# E-P-204-R3_4.net
KiCad netlist of a schematic drawn in EAGLE
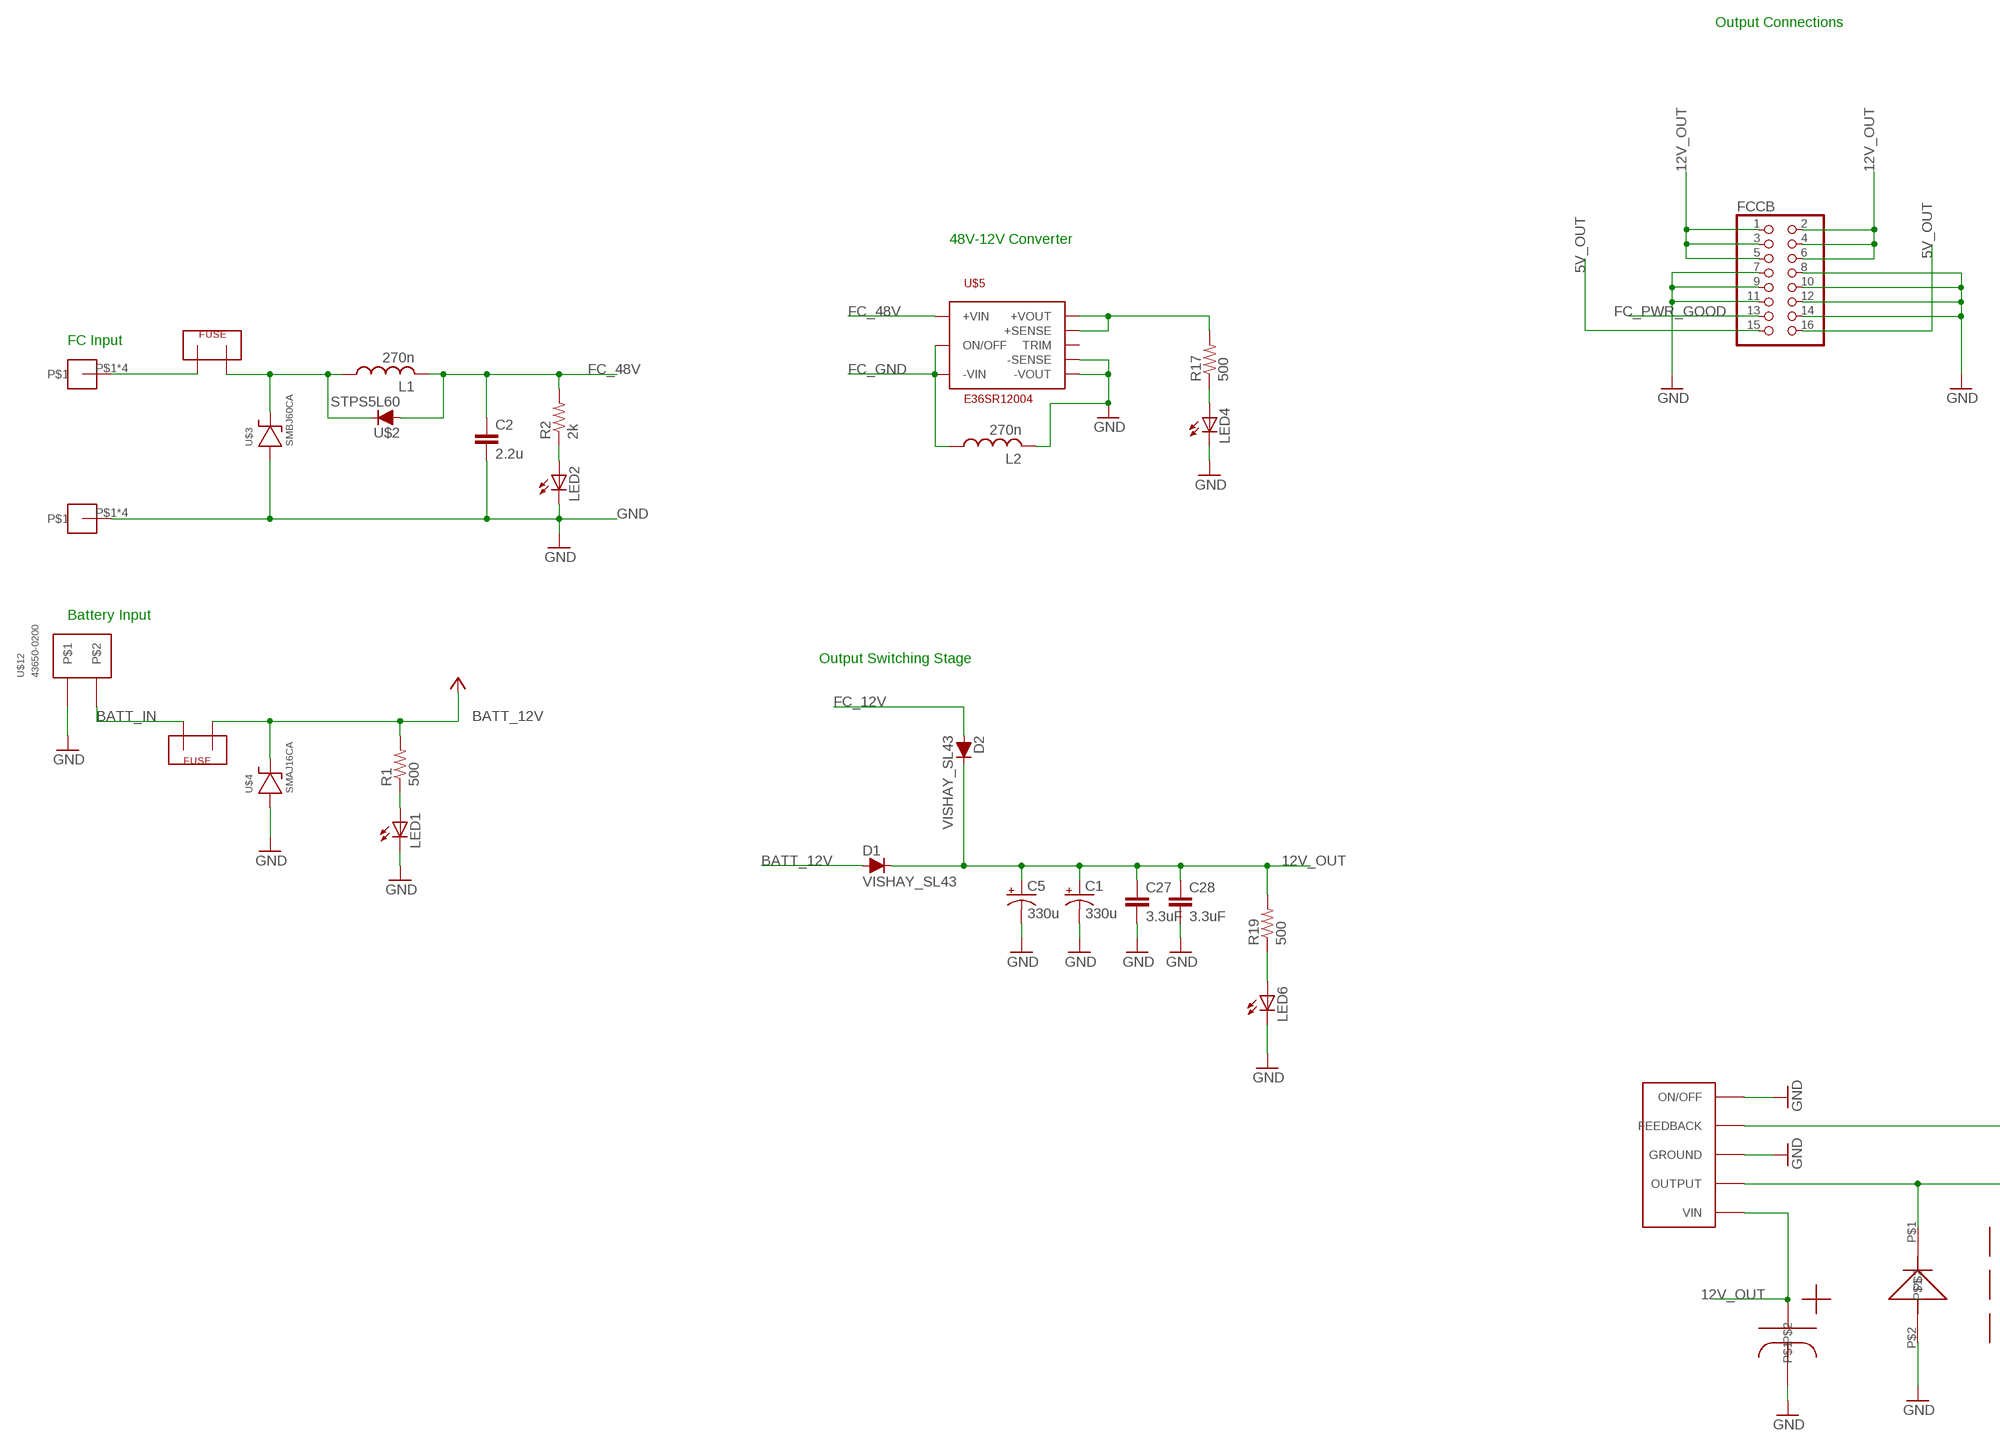
[diagram p0: schematic, sheet 1, part 1 of 2]
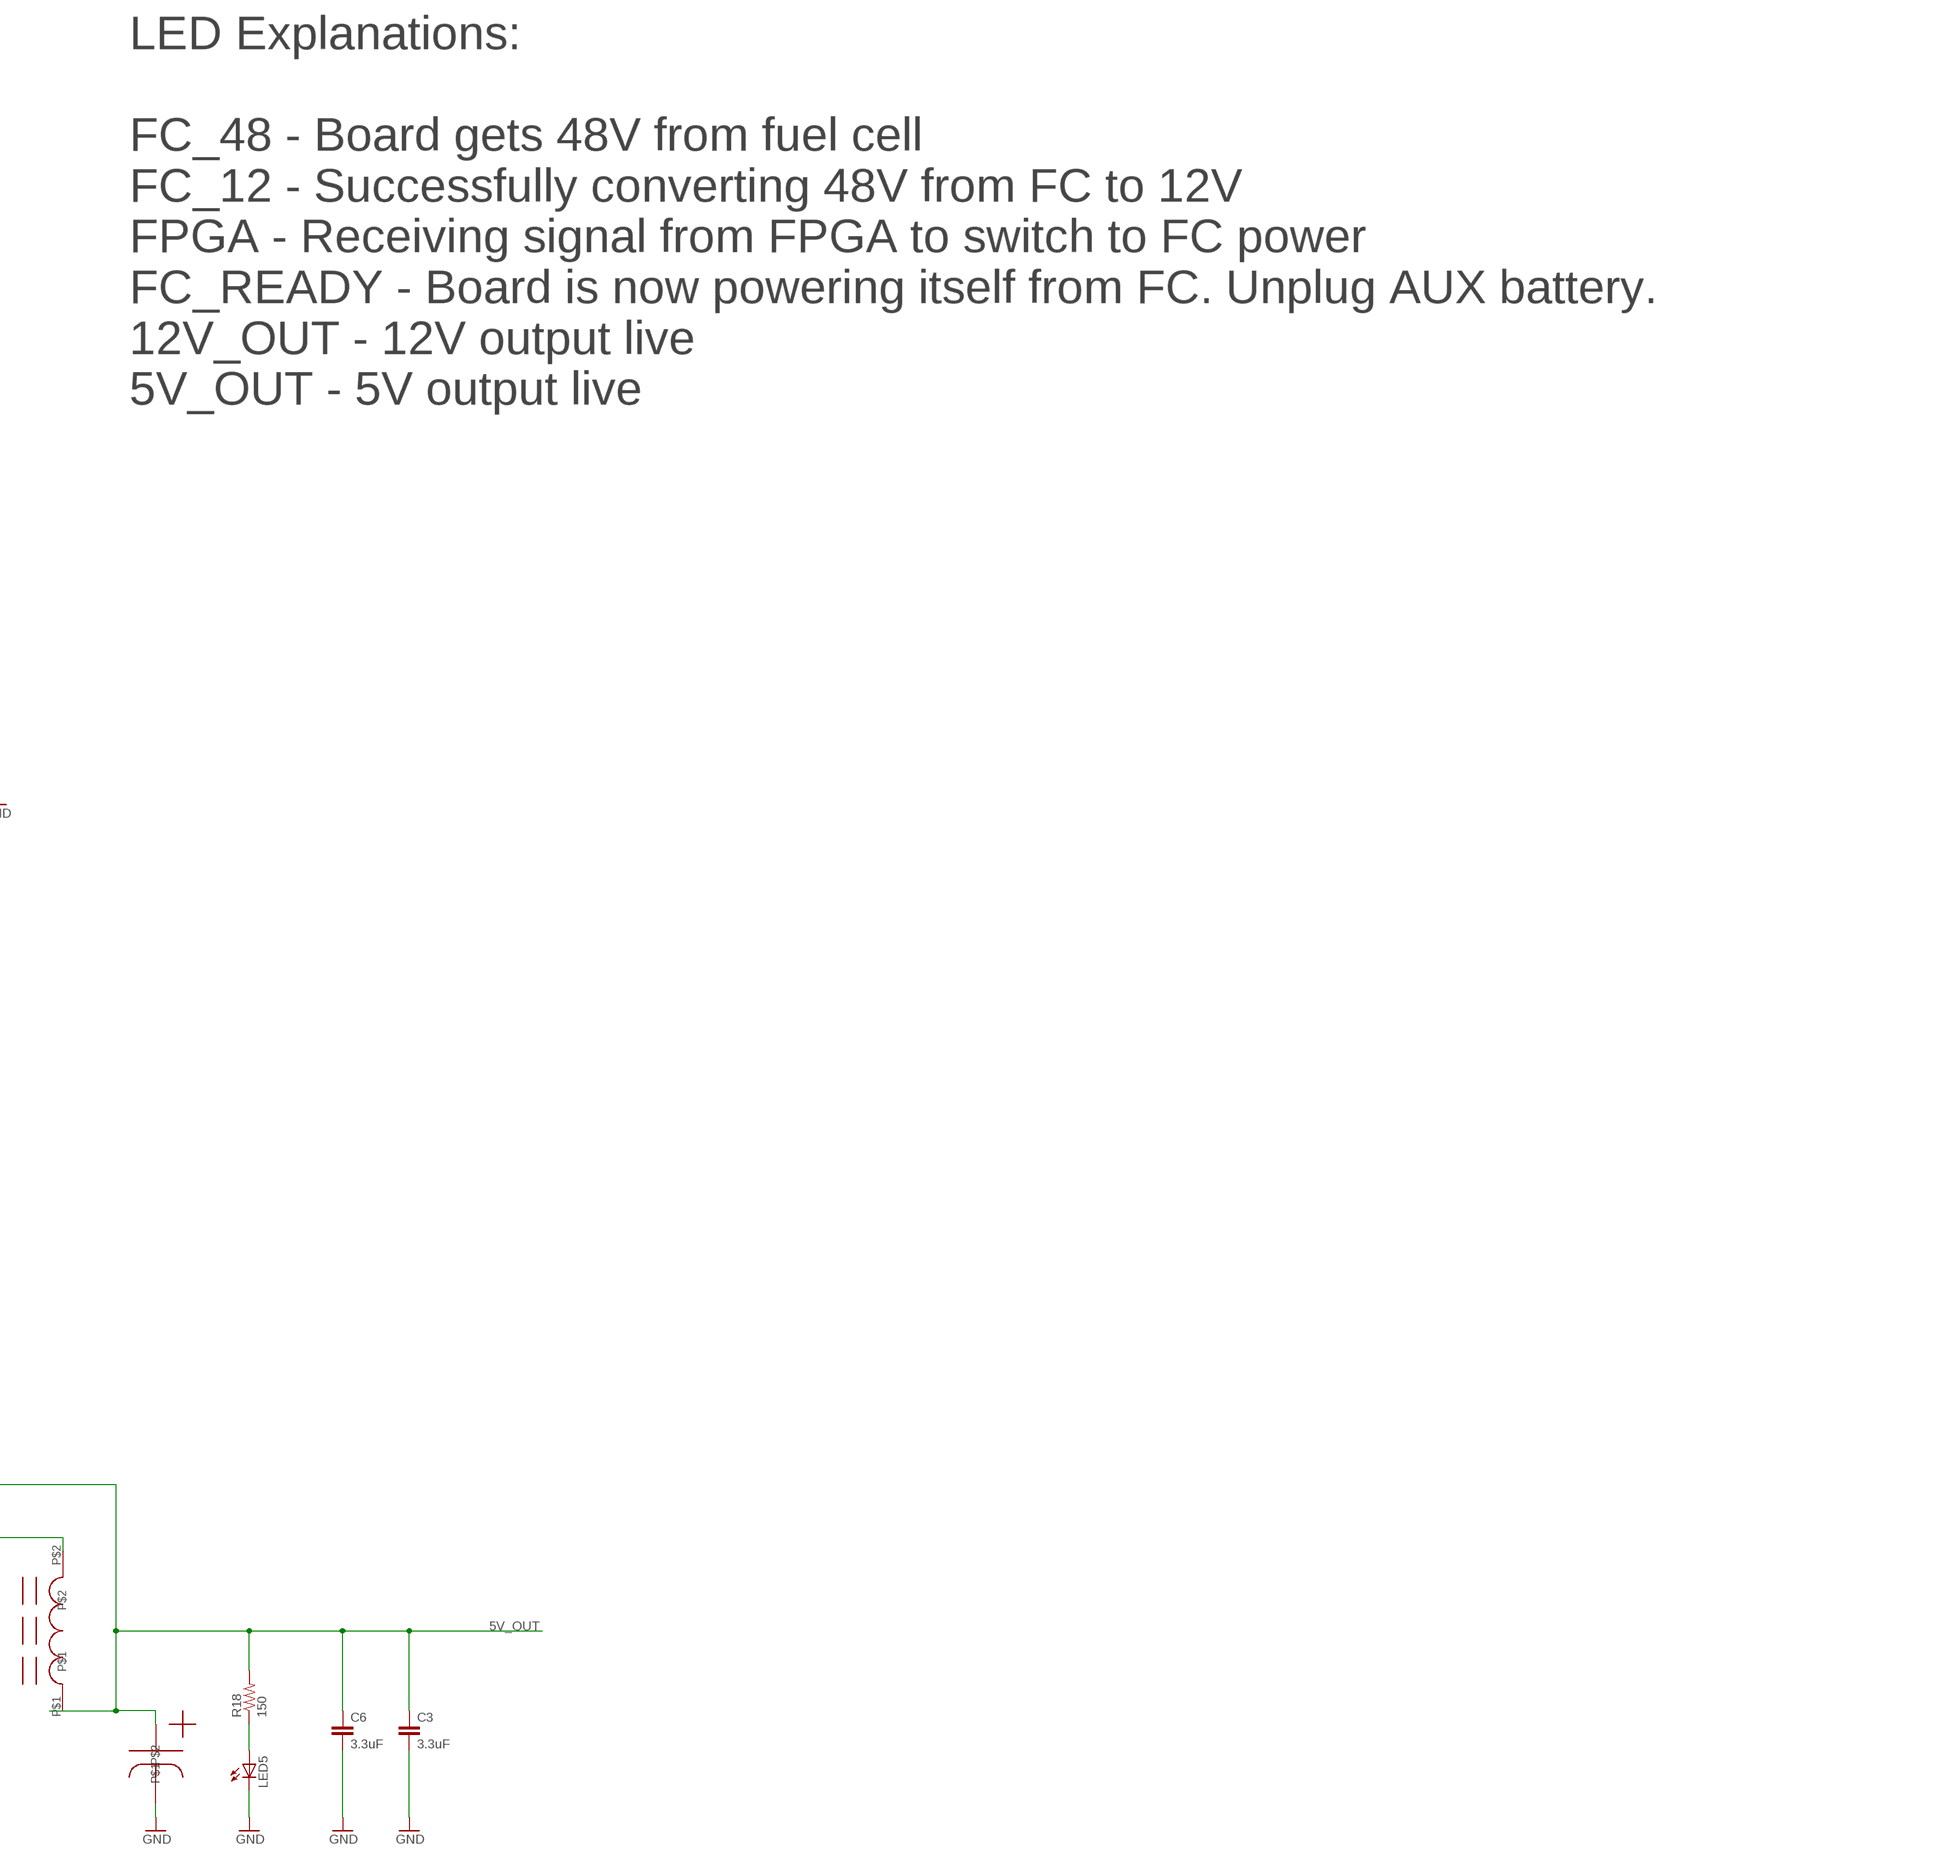
[diagram p1: schematic, sheet 1, part 2 of 2]

(export (version "E")
  (design (tool "Eeschema 10.0.6"))
  (components
    (comp (ref "C1")
      (value "330u")
      (footprint "eagle-import:PANASONIC_E")
      (libsource (lib "eagle-import") (part "CAP_POLE"))
    )
    (comp (ref "C2")
      (value "2.2u")
      (footprint "eagle-import:C1210")
      (libsource (lib "eagle-import") (part "C-EUC1210"))
    )
    (comp (ref "C3")
      (value "3.3uF")
      (footprint "eagle-import:C0805K")
      (libsource (lib "eagle-import") (part "C-EUC0805K"))
    )
    (comp (ref "C5")
      (value "330u")
      (footprint "eagle-import:PANASONIC_E")
      (libsource (lib "eagle-import") (part "CAP_POLE"))
    )
    (comp (ref "C6")
      (value "3.3uF")
      (footprint "eagle-import:C0805K")
      (libsource (lib "eagle-import") (part "C-EUC0805K"))
    )
    (comp (ref "C27")
      (value "3.3uF")
      (footprint "eagle-import:C0805K")
      (libsource (lib "eagle-import") (part "C-EUC0805K"))
    )
    (comp (ref "C28")
      (value "3.3uF")
      (footprint "eagle-import:C0805K")
      (libsource (lib "eagle-import") (part "C-EUC0805K"))
    )
    (comp (ref "D1")
      (value "VISHAY_SL43")
      (footprint "eagle-import:DO-214AB_SMC")
      (libsource (lib "eagle-import") (part "VISHAY_SL43"))
    )
    (comp (ref "D2")
      (value "VISHAY_SL43")
      (footprint "eagle-import:DO-214AB_SMC")
      (libsource (lib "eagle-import") (part "VISHAY_SL43"))
    )
    (comp (ref "FCCB")
      (value "PINHD-2X8")
      (footprint "eagle-import:2X08")
      (libsource (lib "eagle-import") (part "PINHD-2X8"))
    )
    (comp (ref "L1")
      (value "270n")
      (footprint "eagle-import:L3225P")
      (libsource (lib "eagle-import") (part "L-USL3225P"))
    )
    (comp (ref "L2")
      (value "270n")
      (footprint "eagle-import:L3225P")
      (libsource (lib "eagle-import") (part "L-USL3225P"))
    )
    (comp (ref "LED1")
      (value "LED1206")
      (footprint "eagle-import:LED-1206")
      (libsource (lib "eagle-import") (part "LED1206"))
    )
    (comp (ref "LED2")
      (value "LED1206")
      (footprint "eagle-import:LED-1206")
      (libsource (lib "eagle-import") (part "LED1206"))
    )
    (comp (ref "LED4")
      (value "LED1206")
      (footprint "eagle-import:LED-1206")
      (libsource (lib "eagle-import") (part "LED1206"))
    )
    (comp (ref "LED5")
      (value "LED1206")
      (footprint "eagle-import:LED-1206")
      (libsource (lib "eagle-import") (part "LED1206"))
    )
    (comp (ref "LED6")
      (value "LED1206")
      (footprint "eagle-import:LED-1206")
      (libsource (lib "eagle-import") (part "LED1206"))
    )
    (comp (ref "R1")
      (value "500")
      (footprint "eagle-import:M0805")
      (libsource (lib "eagle-import") (part "R-US_M0805"))
    )
    (comp (ref "R2")
      (value "2k")
      (footprint "eagle-import:M0805")
      (libsource (lib "eagle-import") (part "R-US_M0805"))
    )
    (comp (ref "R17")
      (value "500")
      (footprint "eagle-import:M0805")
      (libsource (lib "eagle-import") (part "R-US_M0805"))
    )
    (comp (ref "R18")
      (value "150")
      (footprint "eagle-import:M0805")
      (libsource (lib "eagle-import") (part "R-US_M0805"))
    )
    (comp (ref "R19")
      (value "500")
      (footprint "eagle-import:M0805")
      (libsource (lib "eagle-import") (part "R-US_M0805"))
    )
    (comp (ref "U$2")
      (value "STPS5L60")
      (footprint "eagle-import:STM_SMC")
      (libsource (lib "eagle-import") (part "STPS5L60"))
    )
    (comp (ref "U$3")
      (value "SMBJ60CA")
      (footprint "eagle-import:.277X.089")
      (libsource (lib "eagle-import") (part "SMBJ60CA"))
    )
    (comp (ref "U$4")
      (value "SMAJ16CA")
      (footprint "eagle-import:.25X.07")
      (libsource (lib "eagle-import") (part "SMAJ16CA"))
    )
    (comp (ref "U$5")
      (value "E36SR12004")
      (footprint "eagle-import:2.30X0.90X0.34")
      (libsource (lib "eagle-import") (part "E36SR12004"))
    )
    (comp (ref "U$6")
      (value "SCREW-8191")
      (footprint "eagle-import:SCREW-8191")
      (libsource (lib "eagle-import") (part "SCREW-8191"))
    )
    (comp (ref "U$7")
      (value "FUSEMINI-BLADE")
      (footprint "eagle-import:MINI-BLADE-FUSE")
      (libsource (lib "eagle-import") (part "FUSEMINI-BLADE"))
    )
    (comp (ref "U$8")
      (value "SCREW-8191")
      (footprint "eagle-import:SCREW-8191")
      (libsource (lib "eagle-import") (part "SCREW-8191"))
    )
    (comp (ref "U$9")
      (value "MBR360GOS")
      (footprint "eagle-import:MBR360GOS")
      (libsource (lib "eagle-import") (part "MBR360GOS"))
    )
    (comp (ref "U$10")
      (value "FUSEMINI-BLADE")
      (footprint "eagle-import:MINI-BLADE-FUSE")
      (libsource (lib "eagle-import") (part "FUSEMINI-BLADE"))
    )
    (comp (ref "U$12")
      (value "43650-0200")
      (footprint "eagle-import:43650-0200")
      (libsource (lib "eagle-import") (part "43650-0200"))
    )
    (comp (ref "U$14")
      (value "LM2576")
      (footprint "eagle-import:D2PAK-5")
      (libsource (lib "eagle-import") (part "LM2576"))
    )
    (comp (ref "U$15")
      (value "CAPESK107M025AC3AA")
      (footprint "eagle-import:ESK107M025AC3AA")
      (libsource (lib "eagle-import") (part "CAPESK107M025AC3AA"))
    )
    (comp (ref "U$16")
      (value "CAPESK108M025AH4EA")
      (footprint "eagle-import:ESK108M025AH4EA")
      (libsource (lib "eagle-import") (part "CAPESK108M025AH4EA"))
    )
    (comp (ref "U$17")
      (value "M1418-ND")
      (footprint "eagle-import:M1418-ND")
      (libsource (lib "eagle-import") (part "M1418-ND"))
    )
  )
  (nets
    (net (code "1") (name "+5V") (class "Default")
      (node (ref "D1") (pin "A") (pinfunction "A_A") (pintype "passive"))
      (node (ref "R1") (pin "2") (pinfunction "2_2") (pintype "passive"))
      (node (ref "U$10") (pin "OUT") (pinfunction "OUT_OUT") (pintype "bidirectional"))
      (node (ref "U$4") (pin "CATHODE") (pinfunction "CATHODE_CATHODE") (pintype "bidirectional"))
    )
    (net (code "2") (name "/5V_OUT") (class "Default")
      (node (ref "C3") (pin "1") (pinfunction "1_1") (pintype "passive"))
      (node (ref "C6") (pin "1") (pinfunction "1_1") (pintype "passive"))
      (node (ref "FCCB") (pin "15") (pinfunction "15_15") (pintype "passive"))
      (node (ref "FCCB") (pin "16") (pinfunction "16_16") (pintype "passive"))
      (node (ref "R18") (pin "2") (pinfunction "2_2") (pintype "passive"))
      (node (ref "U$14") (pin "4") (pinfunction "FEEDBACK_4") (pintype "bidirectional"))
      (node (ref "U$16") (pin "P$1") (pinfunction "P$1_P$1") (pintype "bidirectional"))
    )
    (net (code "3") (name "/12V_OUT") (class "Default")
      (node (ref "C1") (pin "+") (pinfunction "+_+") (pintype "passive"))
      (node (ref "C27") (pin "1") (pinfunction "1_1") (pintype "passive"))
      (node (ref "C28") (pin "1") (pinfunction "1_1") (pintype "passive"))
      (node (ref "C5") (pin "+") (pinfunction "+_+") (pintype "passive"))
      (node (ref "D1") (pin "C") (pinfunction "C_C") (pintype "passive"))
      (node (ref "D2") (pin "C") (pinfunction "C_C") (pintype "passive"))
      (node (ref "FCCB") (pin "1") (pinfunction "1_1") (pintype "passive"))
      (node (ref "FCCB") (pin "2") (pinfunction "2_2") (pintype "passive"))
      (node (ref "FCCB") (pin "3") (pinfunction "3_3") (pintype "passive"))
      (node (ref "FCCB") (pin "4") (pinfunction "4_4") (pintype "passive"))
      (node (ref "FCCB") (pin "5") (pinfunction "5_5") (pintype "passive"))
      (node (ref "FCCB") (pin "6") (pinfunction "6_6") (pintype "passive"))
      (node (ref "R19") (pin "2") (pinfunction "2_2") (pintype "passive"))
      (node (ref "U$14") (pin "1") (pinfunction "VIN_1") (pintype "bidirectional"))
      (node (ref "U$15") (pin "P$1") (pinfunction "P$1_P$1") (pintype "bidirectional"))
    )
    (net (code "4") (name "/BATT_IN") (class "Default")
      (node (ref "U$10") (pin "IN") (pinfunction "IN_IN") (pintype "bidirectional"))
      (node (ref "U$12") (pin "P$1") (pinfunction "P$2_P$1") (pintype "bidirectional"))
    )
    (net (code "5") (name "/FC_12V") (class "Default")
      (node (ref "D2") (pin "A") (pinfunction "A_A") (pintype "passive"))
      (node (ref "R17") (pin "2") (pinfunction "2_2") (pintype "passive"))
      (node (ref "U$5") (pin "P$7") (pinfunction "+SENSE_P$7") (pintype "input"))
      (node (ref "U$5") (pin "P$8") (pinfunction "+VOUT_P$8") (pintype "power_in"))
    )
    (net (code "6") (name "/FC_48V") (class "Default")
      (node (ref "C2") (pin "1") (pinfunction "1_1") (pintype "passive"))
      (node (ref "L1") (pin "2") (pinfunction "2_2") (pintype "passive"))
      (node (ref "R2") (pin "2") (pinfunction "2_2") (pintype "passive"))
      (node (ref "U$2") (pin "A") (pinfunction "A_A") (pintype "passive"))
      (node (ref "U$5") (pin "P$1") (pinfunction "+VIN_P$1") (pintype "power_in"))
    )
    (net (code "7") (name "/FC_GND") (class "Default")
      (node (ref "L2") (pin "1") (pinfunction "1_1") (pintype "passive"))
      (node (ref "U$5") (pin "P$2") (pinfunction "ON/OFF_P$2") (pintype "bidirectional"))
      (node (ref "U$5") (pin "P$3") (pinfunction "-VIN_P$3") (pintype "power_in"))
    )
    (net (code "8") (name "/FC_PWR_GOOD") (class "Default")
      (node (ref "FCCB") (pin "13") (pinfunction "13_13") (pintype "passive"))
    )
    (net (code "9") (name "GND") (class "Default")
      (node (ref "C1") (pin "-") (pinfunction "-_-") (pintype "passive"))
      (node (ref "C2") (pin "2") (pinfunction "2_2") (pintype "passive"))
      (node (ref "C27") (pin "2") (pinfunction "2_2") (pintype "passive"))
      (node (ref "C28") (pin "2") (pinfunction "2_2") (pintype "passive"))
      (node (ref "C3") (pin "2") (pinfunction "2_2") (pintype "passive"))
      (node (ref "C5") (pin "-") (pinfunction "-_-") (pintype "passive"))
      (node (ref "C6") (pin "2") (pinfunction "2_2") (pintype "passive"))
      (node (ref "FCCB") (pin "10") (pinfunction "10_10") (pintype "passive"))
      (node (ref "FCCB") (pin "11") (pinfunction "11_11") (pintype "passive"))
      (node (ref "FCCB") (pin "12") (pinfunction "12_12") (pintype "passive"))
      (node (ref "FCCB") (pin "14") (pinfunction "14_14") (pintype "passive"))
      (node (ref "FCCB") (pin "7") (pinfunction "7_7") (pintype "passive"))
      (node (ref "FCCB") (pin "8") (pinfunction "8_8") (pintype "passive"))
      (node (ref "FCCB") (pin "9") (pinfunction "9_9") (pintype "passive"))
      (node (ref "L2") (pin "2") (pinfunction "2_2") (pintype "passive"))
      (node (ref "LED1") (pin "C") (pinfunction "C_C") (pintype "passive"))
      (node (ref "LED2") (pin "C") (pinfunction "C_C") (pintype "passive"))
      (node (ref "LED4") (pin "C") (pinfunction "C_C") (pintype "passive"))
      (node (ref "LED5") (pin "C") (pinfunction "C_C") (pintype "passive"))
      (node (ref "LED6") (pin "C") (pinfunction "C_C") (pintype "passive"))
      (node (ref "U$12") (pin "P$2") (pinfunction "P$1_P$2") (pintype "bidirectional"))
      (node (ref "U$14") (pin "3") (pinfunction "GROUND_3") (pintype "bidirectional"))
      (node (ref "U$14") (pin "5") (pinfunction "ON/OFF_5") (pintype "bidirectional"))
      (node (ref "U$14") (pin "GROUND") (pinfunction "GROUND_GROUND") (pintype "bidirectional"))
      (node (ref "U$15") (pin "P$2") (pinfunction "P$2_P$2") (pintype "bidirectional"))
      (node (ref "U$16") (pin "P$2") (pinfunction "P$2_P$2") (pintype "bidirectional"))
      (node (ref "U$3") (pin "ANODE") (pinfunction "ANODE_ANODE") (pintype "bidirectional"))
      (node (ref "U$4") (pin "ANODE") (pinfunction "ANODE_ANODE") (pintype "bidirectional"))
      (node (ref "U$5") (pin "P$4") (pinfunction "-VOUT_P$4") (pintype "power_in"))
      (node (ref "U$5") (pin "P$5") (pinfunction "-SENSE_P$5") (pintype "input"))
      (node (ref "U$6") (pin "P$1") (pinfunction "P$1_P$1") (pintype "bidirectional"))
      (node (ref "U$6") (pin "P$2") (pinfunction "P$1_P$2") (pintype "bidirectional"))
      (node (ref "U$6") (pin "P$3") (pinfunction "P$1_P$3") (pintype "bidirectional"))
      (node (ref "U$6") (pin "P$4") (pinfunction "P$1_P$4") (pintype "bidirectional"))
      (node (ref "U$9") (pin "P$2") (pinfunction "P$1_P$2") (pintype "bidirectional"))
    )
    (net (code "10") (name "Net-(L1-Pad1)") (class "Default")
      (node (ref "L1") (pin "1") (pinfunction "1_1") (pintype "passive"))
      (node (ref "U$2") (pin "C") (pinfunction "C_C") (pintype "passive"))
      (node (ref "U$3") (pin "CATHODE") (pinfunction "CATHODE_CATHODE") (pintype "bidirectional"))
      (node (ref "U$7") (pin "IN") (pinfunction "IN_IN") (pintype "bidirectional"))
    )
    (net (code "11") (name "Net-(LED1-PadA)") (class "Default")
      (node (ref "LED1") (pin "A") (pinfunction "A_A") (pintype "passive"))
      (node (ref "R1") (pin "1") (pinfunction "1_1") (pintype "passive"))
    )
    (net (code "12") (name "Net-(LED2-PadA)") (class "Default")
      (node (ref "LED2") (pin "A") (pinfunction "A_A") (pintype "passive"))
      (node (ref "R2") (pin "1") (pinfunction "1_1") (pintype "passive"))
    )
    (net (code "13") (name "Net-(LED4-PadA)") (class "Default")
      (node (ref "LED4") (pin "A") (pinfunction "A_A") (pintype "passive"))
      (node (ref "R17") (pin "1") (pinfunction "1_1") (pintype "passive"))
    )
    (net (code "14") (name "Net-(LED5-PadA)") (class "Default")
      (node (ref "LED5") (pin "A") (pinfunction "A_A") (pintype "passive"))
      (node (ref "R18") (pin "1") (pinfunction "1_1") (pintype "passive"))
    )
    (net (code "15") (name "Net-(LED6-PadA)") (class "Default")
      (node (ref "LED6") (pin "A") (pinfunction "A_A") (pintype "passive"))
      (node (ref "R19") (pin "1") (pinfunction "1_1") (pintype "passive"))
    )
    (net (code "16") (name "Net-(U$7-PadOUT)") (class "Default")
      (node (ref "U$7") (pin "OUT") (pinfunction "OUT_OUT") (pintype "bidirectional"))
      (node (ref "U$8") (pin "P$1") (pinfunction "P$1_P$1") (pintype "bidirectional"))
      (node (ref "U$8") (pin "P$2") (pinfunction "P$1_P$2") (pintype "bidirectional"))
      (node (ref "U$8") (pin "P$3") (pinfunction "P$1_P$3") (pintype "bidirectional"))
      (node (ref "U$8") (pin "P$4") (pinfunction "P$1_P$4") (pintype "bidirectional"))
    )
    (net (code "17") (name "Net-(U$14-OUTPUT)") (class "Default")
      (node (ref "U$14") (pin "2") (pinfunction "OUTPUT_2") (pintype "bidirectional"))
      (node (ref "U$17") (pin "P$2") (pinfunction "P$2_P$2") (pintype "bidirectional"))
      (node (ref "U$9") (pin "P$1") (pinfunction "P$2_P$1") (pintype "bidirectional"))
    )
    (net (code "18") (name "unconnected-(U$5-TRIM-PadP$6)") (class "Default")
      (node (ref "U$5") (pin "P$6") (pinfunction "TRIM_P$6") (pintype "bidirectional"))
    )
    (net (code "19") (name "unconnected-(U$17-PadP$1)") (class "Default")
      (node (ref "U$17") (pin "P$1") (pinfunction "P$1_P$1") (pintype "bidirectional"))
    )
  )
)
